# Sheet2_Inverter_GateDriver.net
KiCad netlist of a schematic drawn in Altium Designer
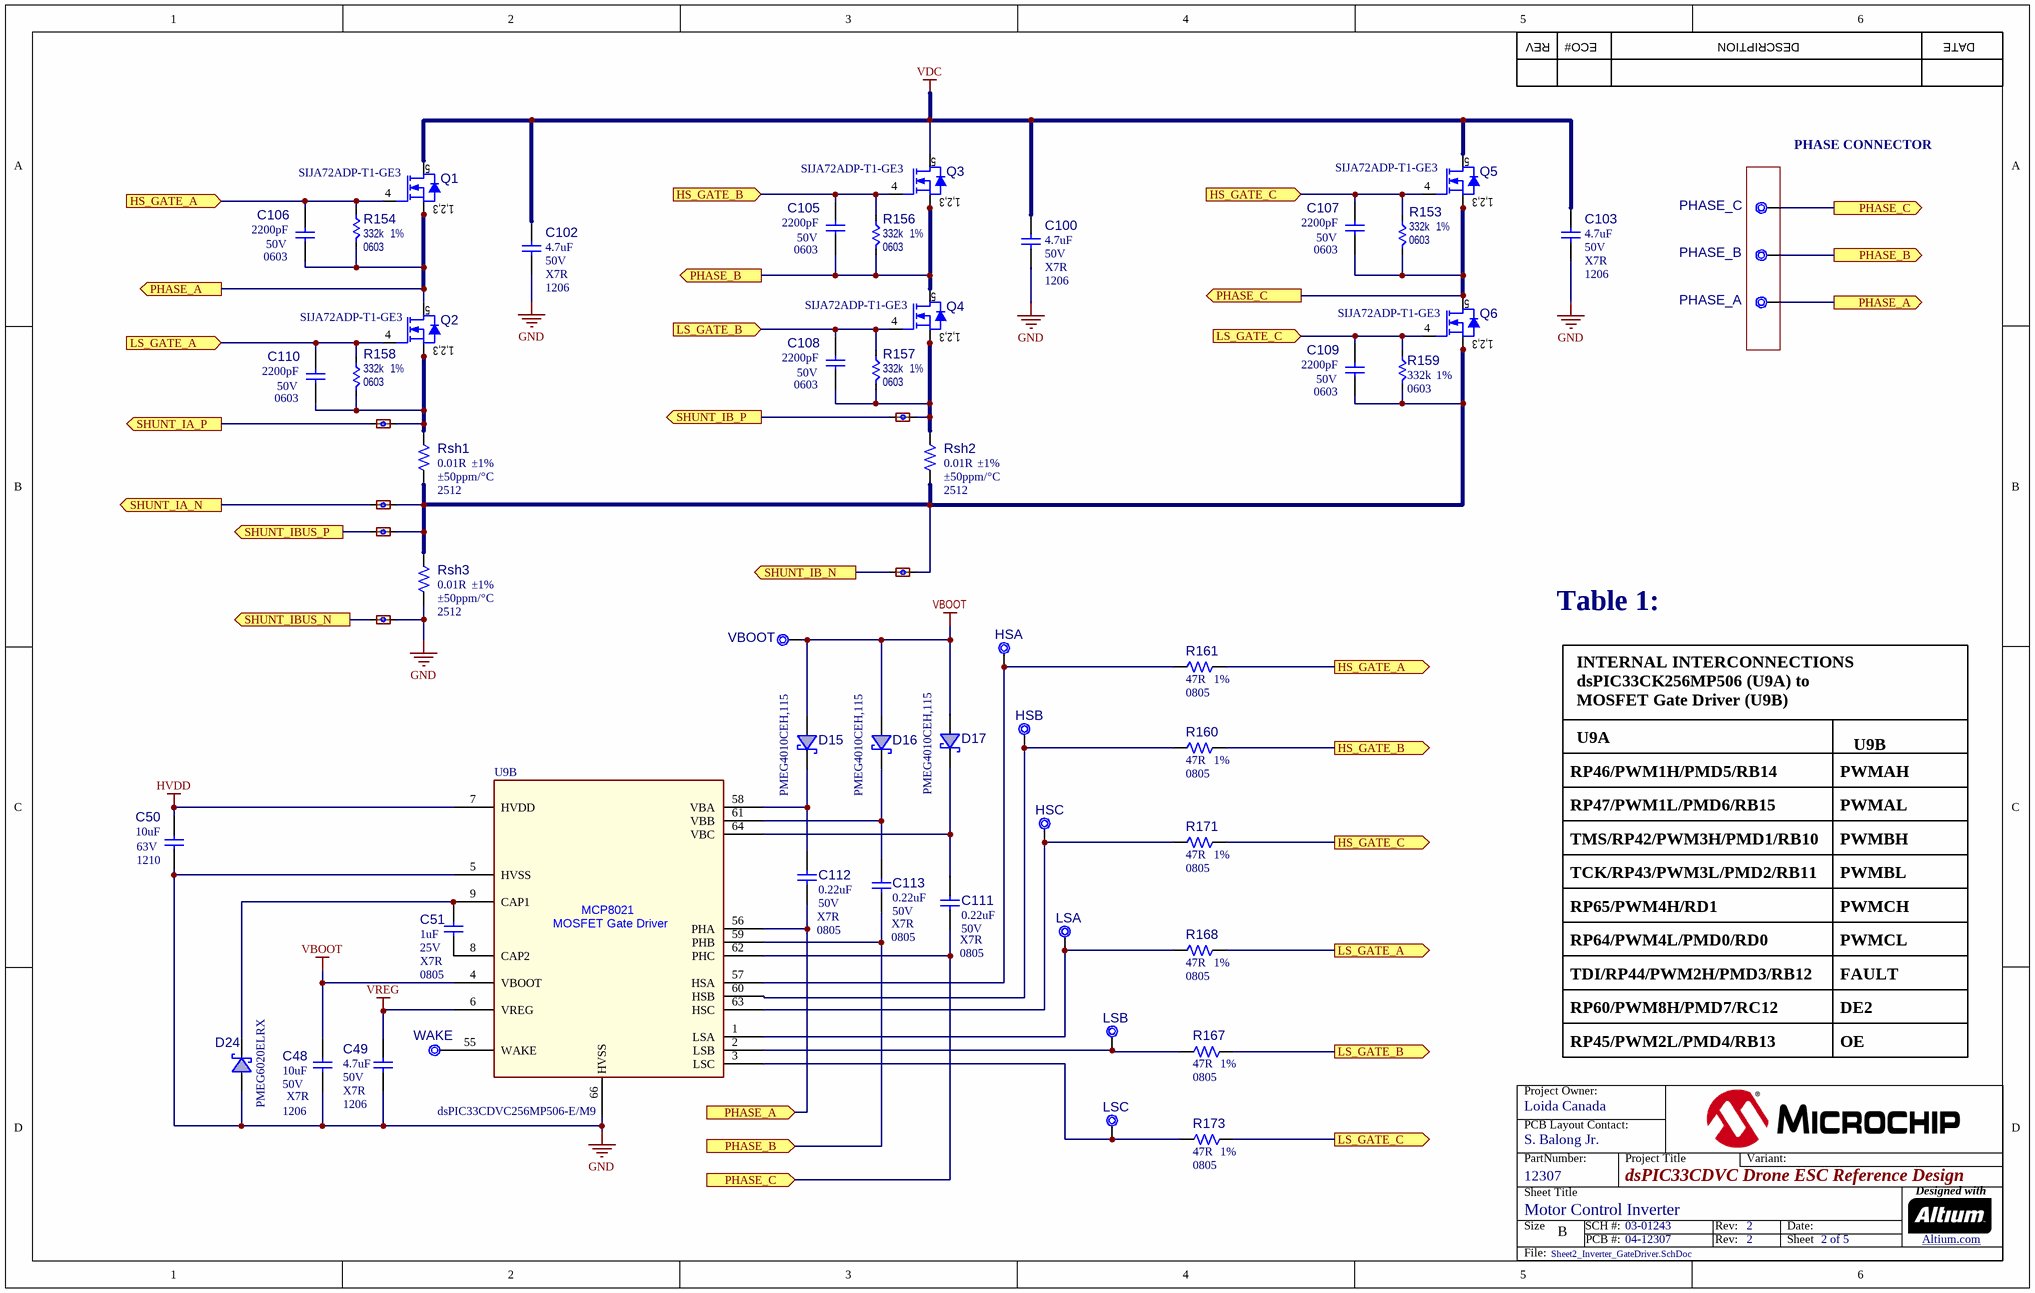
[diagram p0: Sheet2_Inverter_GateDriver.SchDoc]

(export (version "E")
  (design (tool "Eeschema 10.0.6"))
  (components
    (comp (ref "C48")
      (value "10uF")
      (footprint "CAP_C_1206")
      (fields
        (field (name "VOLTAGE") "50V")
        (field (name "PACKAGE") "1206")
        (field (name "TEMPERATURE COEFFICIENT") "X7R")
        (field (name "Comment") "Capacitor NP")
        (field (name "OWNER") "Sam Charles")
      )
      (libsource (lib "MCHP-CDB") (part "Capacitor NP"))
    )
    (comp (ref "C49")
      (value "4.7uF")
      (footprint "CAP_C_1206")
      (description "Capacitor")
      (fields
        (field (name "VOLTAGE") "50V")
        (field (name "PACKAGE") "1206")
        (field (name "TOLERANCE") "10%")
        (field (name "TEMPERATURE COEFFCIENT") "X7R")
        (field (name "Comment") "Capacitor NP")
        (field (name "OWNER") "Jairuz Agang-ang")
      )
      (libsource (lib "MCHP-CDB") (part "Capacitor NP"))
    )
    (comp (ref "C50")
      (value "10uF")
      (footprint "CAP_C_1210")
      (fields
        (field (name "VOLTAGE") "63V")
        (field (name "PACKAGE") "1210")
        (field (name "TOLERANCE") "10%")
        (field (name "Comment") "Capacitor NP")
        (field (name "OWNER") "Narasimha Murthy")
      )
      (libsource (lib "MCHP-CDB") (part "Capacitor NP"))
    )
    (comp (ref "C51")
      (value "1uF")
      (footprint "CAP_C_0805")
      (description "Capacitor")
      (fields
        (field (name "VOLTAGE") "25V")
        (field (name "PACKAGE") "0805")
        (field (name "TOLERANCE") "10%")
        (field (name "TEMPERATURE COEFFCIENT") "X7R")
        (field (name "Comment") "Capacitor NP")
        (field (name "OWNER") "Tad Ahlvers")
      )
      (libsource (lib "") (part "Capacitor NP_1"))
    )
    (comp (ref "C100")
      (value "4.7uF")
      (footprint "CAP_C_1206")
      (description "Capacitor")
      (fields
        (field (name "VOLTAGE") "50V")
        (field (name "PACKAGE") "1206")
        (field (name "TOLERANCE") "10%")
        (field (name "TEMPERATURE COEFFCIENT") "X7R")
        (field (name "Comment") "Capacitor NP")
        (field (name "OWNER") "Jairuz Agang-ang")
      )
      (libsource (lib "MCHP-CDB") (part "Capacitor NP"))
    )
    (comp (ref "C102")
      (value "4.7uF")
      (footprint "CAP_C_1206")
      (description "Capacitor")
      (fields
        (field (name "VOLTAGE") "50V")
        (field (name "PACKAGE") "1206")
        (field (name "TOLERANCE") "10%")
        (field (name "TEMPERATURE COEFFCIENT") "X7R")
        (field (name "Comment") "Capacitor NP")
        (field (name "OWNER") "Jairuz Agang-ang")
      )
      (libsource (lib "MCHP-CDB") (part "Capacitor NP"))
    )
    (comp (ref "C103")
      (value "4.7uF")
      (footprint "CAP_C_1206")
      (description "Capacitor")
      (fields
        (field (name "VOLTAGE") "50V")
        (field (name "PACKAGE") "1206")
        (field (name "TOLERANCE") "10%")
        (field (name "TEMPERATURE COEFFCIENT") "X7R")
        (field (name "Comment") "Capacitor NP")
        (field (name "OWNER") "Jairuz Agang-ang")
      )
      (libsource (lib "MCHP-CDB") (part "Capacitor NP"))
    )
    (comp (ref "C105")
      (value "2200pF")
      (footprint "CAP_C_0603")
      (fields
        (field (name "VOLTAGE") "50V")
        (field (name "PACKAGE") "0603")
        (field (name "TOLERANCE") "10%")
        (field (name "Comment") "Capacitor NP")
      )
      (libsource (lib "MCHP-CDB") (part "Capacitor NP"))
    )
    (comp (ref "C106")
      (value "2200pF")
      (footprint "CAP_C_0603")
      (fields
        (field (name "VOLTAGE") "50V")
        (field (name "PACKAGE") "0603")
        (field (name "TOLERANCE") "10%")
        (field (name "Comment") "Capacitor NP")
      )
      (libsource (lib "MCHP-CDB") (part "Capacitor NP"))
    )
    (comp (ref "C107")
      (value "2200pF")
      (footprint "CAP_C_0603")
      (fields
        (field (name "VOLTAGE") "50V")
        (field (name "PACKAGE") "0603")
        (field (name "TOLERANCE") "10%")
        (field (name "Comment") "Capacitor NP")
      )
      (libsource (lib "MCHP-CDB") (part "Capacitor NP"))
    )
    (comp (ref "C108")
      (value "2200pF")
      (footprint "CAP_C_0603")
      (fields
        (field (name "VOLTAGE") "50V")
        (field (name "PACKAGE") "0603")
        (field (name "TOLERANCE") "10%")
        (field (name "Comment") "Capacitor NP")
      )
      (libsource (lib "MCHP-CDB") (part "Capacitor NP"))
    )
    (comp (ref "C109")
      (value "2200pF")
      (footprint "CAP_C_0603")
      (fields
        (field (name "VOLTAGE") "50V")
        (field (name "PACKAGE") "0603")
        (field (name "TOLERANCE") "10%")
        (field (name "Comment") "Capacitor NP")
      )
      (libsource (lib "MCHP-CDB") (part "Capacitor NP"))
    )
    (comp (ref "C110")
      (value "2200pF")
      (footprint "CAP_C_0603")
      (fields
        (field (name "VOLTAGE") "50V")
        (field (name "PACKAGE") "0603")
        (field (name "TOLERANCE") "10%")
        (field (name "Comment") "Capacitor NP")
      )
      (libsource (lib "MCHP-CDB") (part "Capacitor NP"))
    )
    (comp (ref "C111")
      (value "0.22uF")
      (footprint "CAP_C_0805")
      (description "Capacitor")
      (fields
        (field (name "VOLTAGE") "50V")
        (field (name "PACKAGE") "0805")
        (field (name "TOLERANCE") "10%")
        (field (name "TEMPERATURE COEFFCIENT") "X7R")
        (field (name "Comment") "Capacitor NP")
      )
      (libsource (lib "MCHP-CDB") (part "Capacitor NP"))
    )
    (comp (ref "C112")
      (value "0.22uF")
      (footprint "CAP_C_0805")
      (description "Capacitor")
      (fields
        (field (name "VOLTAGE") "50V")
        (field (name "PACKAGE") "0805")
        (field (name "TOLERANCE") "10%")
        (field (name "TEMPERATURE COEFFCIENT") "X7R")
        (field (name "Comment") "Capacitor NP")
      )
      (libsource (lib "MCHP-CDB") (part "Capacitor NP"))
    )
    (comp (ref "C113")
      (value "0.22uF")
      (footprint "CAP_C_0805")
      (description "Capacitor")
      (fields
        (field (name "VOLTAGE") "50V")
        (field (name "PACKAGE") "0805")
        (field (name "TOLERANCE") "10%")
        (field (name "TEMPERATURE COEFFCIENT") "X7R")
        (field (name "Comment") "Capacitor NP")
      )
      (libsource (lib "MCHP-CDB") (part "Capacitor NP"))
    )
    (comp (ref "D15")
      (value "PMEG4010CEH,115")
      (footprint "SOD-123")
      (fields (field (name "Comment") "Diode Schottky") (field (name "OWNER") "Narasimha Murthy"))
      (libsource (lib "MCHP-CDB") (part "Diode Schottky"))
    )
    (comp (ref "D16")
      (value "PMEG4010CEH,115")
      (footprint "SOD-123")
      (fields (field (name "Comment") "Diode Schottky") (field (name "OWNER") "Narasimha Murthy"))
      (libsource (lib "MCHP-CDB") (part "Diode Schottky"))
    )
    (comp (ref "D17")
      (value "PMEG4010CEH,115")
      (footprint "SOD-123")
      (fields (field (name "Comment") "Diode Schottky") (field (name "OWNER") "Narasimha Murthy"))
      (libsource (lib "MCHP-CDB") (part "Diode Schottky"))
    )
    (comp (ref "D24")
      (value "PMEG6020ELRX")
      (footprint "SOD-123W")
      (fields (field (name "Comment") "Diode Schottky") (field (name "OWNER") "Narasimha Murthy"))
      (libsource (lib "MCHP-CDB") (part "Diode Schottky"))
    )
    (comp (ref "HSA")
      (value "Test Point No BOM")
      (footprint "TP_TH_0.7PADX0.4HOLE")
      (description "Test Point")
      (fields (field (name "OWNER") "Severino Balong Jr."))
      (libsource (lib "MCHP-CDB") (part "Test Point No BOM"))
    )
    (comp (ref "HSB")
      (value "Test Point No BOM")
      (footprint "TP_TH_0.7PADX0.4HOLE")
      (description "Test Point")
      (fields (field (name "OWNER") "Severino Balong Jr."))
      (libsource (lib "MCHP-CDB") (part "Test Point No BOM"))
    )
    (comp (ref "HSC")
      (value "Test Point No BOM")
      (footprint "TP_TH_0.7PADX0.4HOLE")
      (description "Test Point")
      (fields (field (name "OWNER") "Severino Balong Jr."))
      (libsource (lib "MCHP-CDB") (part "Test Point No BOM"))
    )
    (comp (ref "LSA")
      (value "Test Point No BOM")
      (footprint "TP_TH_0.7PADX0.4HOLE")
      (description "Test Point")
      (fields (field (name "OWNER") "Severino Balong Jr."))
      (libsource (lib "MCHP-CDB") (part "Test Point No BOM"))
    )
    (comp (ref "LSB")
      (value "Test Point No BOM")
      (footprint "TP_TH_0.7PADX0.4HOLE")
      (description "Test Point")
      (fields (field (name "OWNER") "Severino Balong Jr."))
      (libsource (lib "MCHP-CDB") (part "Test Point No BOM"))
    )
    (comp (ref "LSC")
      (value "Test Point No BOM")
      (footprint "TP_TH_0.7PADX0.4HOLE")
      (description "Test Point")
      (fields (field (name "OWNER") "Severino Balong Jr."))
      (libsource (lib "MCHP-CDB") (part "Test Point No BOM"))
    )
    (comp (ref "NT1")
      (value "Net Tie")
      (footprint "NET_TIE_0.2mmx0.5mm")
      (fields (field (name "OWNER") "Cristina Salanti"))
      (libsource (lib "MCHP-CDB") (part "Net Tie"))
    )
    (comp (ref "NT2")
      (value "Net Tie")
      (footprint "NET_TIE_0.2mmx0.5mm")
      (fields (field (name "OWNER") "Cristina Salanti"))
      (libsource (lib "MCHP-CDB") (part "Net Tie"))
    )
    (comp (ref "NT3")
      (value "Net Tie")
      (footprint "NET_TIE_0.2mmx0.5mm")
      (fields (field (name "OWNER") "Cristina Salanti"))
      (libsource (lib "MCHP-CDB") (part "Net Tie"))
    )
    (comp (ref "NT4")
      (value "Net Tie")
      (footprint "NET_TIE_0.2mmx0.5mm")
      (fields (field (name "OWNER") "Cristina Salanti"))
      (libsource (lib "MCHP-CDB") (part "Net Tie"))
    )
    (comp (ref "NT5")
      (value "Net Tie")
      (footprint "NET_TIE_0.2mmx0.5mm")
      (fields (field (name "OWNER") "Cristina Salanti"))
      (libsource (lib "MCHP-CDB") (part "Net Tie"))
    )
    (comp (ref "NT6")
      (value "Net Tie")
      (footprint "NET_TIE_0.2mmx0.5mm")
      (fields (field (name "OWNER") "Cristina Salanti"))
      (libsource (lib "MCHP-CDB") (part "Net Tie"))
    )
    (comp (ref "PHASE_A")
      (value "Test Point No BOM")
      (footprint "TP_3.0X2.3X1.3HOLE")
      (description "Test Point")
      (fields (field (name "OWNER") "Severino Balong Jr."))
      (libsource (lib "MCHP-CDB") (part "Test Point No BOM"))
    )
    (comp (ref "PHASE_B")
      (value "Test Point No BOM")
      (footprint "TP_3.0X2.3X1.3HOLE")
      (description "Test Point")
      (fields (field (name "OWNER") "Severino Balong Jr."))
      (libsource (lib "MCHP-CDB") (part "Test Point No BOM"))
    )
    (comp (ref "PHASE_C")
      (value "Test Point No BOM")
      (footprint "TP_3.0X2.3X1.3HOLE")
      (description "Test Point")
      (fields (field (name "OWNER") "Severino Balong Jr."))
      (libsource (lib "MCHP-CDB") (part "Test Point No BOM"))
    )
    (comp (ref "Q1")
      (value "SIJA72ADP-T1-GE3")
      (footprint "PPAK_SO-8L")
      (description "Transistor MOS")
      (fields
        (field (name "POWER") "4.8W")
        (field (name "VOLTAGE") "40V")
        (field (name "OWNER") "Cristina Salanti")
      )
      (libsource (lib "MCHP-CDB") (part "Transistor MOS-N SSSGD"))
    )
    (comp (ref "Q2")
      (value "SIJA72ADP-T1-GE3")
      (footprint "PPAK_SO-8L")
      (description "Transistor MOS")
      (fields
        (field (name "POWER") "4.8W")
        (field (name "VOLTAGE") "40V")
        (field (name "OWNER") "Cristina Salanti")
      )
      (libsource (lib "MCHP-CDB") (part "Transistor MOS-N SSSGD"))
    )
    (comp (ref "Q3")
      (value "SIJA72ADP-T1-GE3")
      (footprint "PPAK_SO-8L")
      (description "Transistor MOS")
      (fields
        (field (name "POWER") "4.8W")
        (field (name "VOLTAGE") "40V")
        (field (name "OWNER") "Cristina Salanti")
      )
      (libsource (lib "MCHP-CDB") (part "Transistor MOS-N SSSGD"))
    )
    (comp (ref "Q4")
      (value "SIJA72ADP-T1-GE3")
      (footprint "PPAK_SO-8L")
      (description "Transistor MOS")
      (fields
        (field (name "POWER") "4.8W")
        (field (name "VOLTAGE") "40V")
        (field (name "OWNER") "Cristina Salanti")
      )
      (libsource (lib "MCHP-CDB") (part "Transistor MOS-N SSSGD"))
    )
    (comp (ref "Q5")
      (value "SIJA72ADP-T1-GE3")
      (footprint "PPAK_SO-8L")
      (description "Transistor MOS")
      (fields
        (field (name "POWER") "4.8W")
        (field (name "VOLTAGE") "40V")
        (field (name "OWNER") "Cristina Salanti")
      )
      (libsource (lib "MCHP-CDB") (part "Transistor MOS-N SSSGD"))
    )
    (comp (ref "Q6")
      (value "SIJA72ADP-T1-GE3")
      (footprint "PPAK_SO-8L")
      (description "Transistor MOS")
      (fields
        (field (name "POWER") "4.8W")
        (field (name "VOLTAGE") "40V")
        (field (name "OWNER") "Cristina Salanti")
      )
      (libsource (lib "MCHP-CDB") (part "Transistor MOS-N SSSGD"))
    )
    (comp (ref "R153")
      (value "332k")
      (footprint "RES_C_0603")
      (description "Resistor")
      (fields
        (field (name "PACKAGE") "0603")
        (field (name "TOLERANCE") "1%")
        (field (name "VOLTAGE") "75V")
        (field (name "POWER") "1/10W")
        (field (name "OWNER") "Bogdan P (M91398)")
      )
      (libsource (lib "") (part "Resistor_1"))
    )
    (comp (ref "R154")
      (value "332k")
      (footprint "RES_C_0603")
      (description "Resistor")
      (fields
        (field (name "PACKAGE") "0603")
        (field (name "TOLERANCE") "1%")
        (field (name "VOLTAGE") "75V")
        (field (name "POWER") "1/10W")
        (field (name "OWNER") "Bogdan P (M91398)")
      )
      (libsource (lib "") (part "Resistor_1"))
    )
    (comp (ref "R156")
      (value "332k")
      (footprint "RES_C_0603")
      (description "Resistor")
      (fields
        (field (name "PACKAGE") "0603")
        (field (name "TOLERANCE") "1%")
        (field (name "VOLTAGE") "75V")
        (field (name "POWER") "1/10W")
        (field (name "OWNER") "Bogdan P (M91398)")
      )
      (libsource (lib "") (part "Resistor_1"))
    )
    (comp (ref "R157")
      (value "332k")
      (footprint "RES_C_0603")
      (description "Resistor")
      (fields
        (field (name "PACKAGE") "0603")
        (field (name "TOLERANCE") "1%")
        (field (name "VOLTAGE") "75V")
        (field (name "POWER") "1/10W")
        (field (name "OWNER") "Bogdan P (M91398)")
      )
      (libsource (lib "") (part "Resistor_1"))
    )
    (comp (ref "R158")
      (value "332k")
      (footprint "RES_C_0603")
      (description "Resistor")
      (fields
        (field (name "PACKAGE") "0603")
        (field (name "TOLERANCE") "1%")
        (field (name "VOLTAGE") "75V")
        (field (name "POWER") "1/10W")
        (field (name "OWNER") "Bogdan P (M91398)")
      )
      (libsource (lib "") (part "Resistor_1"))
    )
    (comp (ref "R159")
      (value "332k")
      (footprint "RES_C_0603")
      (description "Resistor")
      (fields
        (field (name "PACKAGE") "0603")
        (field (name "TOLERANCE") "1%")
        (field (name "VOLTAGE") "75V")
        (field (name "POWER") "1/10W")
        (field (name "OWNER") "Bogdan P (M91398)")
      )
      (libsource (lib "") (part "Resistor_1"))
    )
    (comp (ref "R160")
      (value "47R")
      (footprint "RES_C_0805")
      (description "Resistor")
      (fields
        (field (name "PACKAGE") "0805")
        (field (name "TOLERANCE") "1%")
        (field (name "POWER") "1/8W")
        (field (name "OWNER") "Henry de Villiers")
      )
      (libsource (lib "MCHP-CDB") (part "Resistor"))
    )
    (comp (ref "R161")
      (value "47R")
      (footprint "RES_C_0805")
      (description "Resistor")
      (fields
        (field (name "PACKAGE") "0805")
        (field (name "TOLERANCE") "1%")
        (field (name "POWER") "1/8W")
        (field (name "OWNER") "Henry de Villiers")
      )
      (libsource (lib "MCHP-CDB") (part "Resistor"))
    )
    (comp (ref "R167")
      (value "47R")
      (footprint "RES_C_0805")
      (description "Resistor")
      (fields
        (field (name "PACKAGE") "0805")
        (field (name "TOLERANCE") "1%")
        (field (name "POWER") "1/8W")
        (field (name "OWNER") "Henry de Villiers")
      )
      (libsource (lib "MCHP-CDB") (part "Resistor"))
    )
    (comp (ref "R168")
      (value "47R")
      (footprint "RES_C_0805")
      (description "Resistor")
      (fields
        (field (name "PACKAGE") "0805")
        (field (name "TOLERANCE") "1%")
        (field (name "POWER") "1/8W")
        (field (name "OWNER") "Henry de Villiers")
      )
      (libsource (lib "MCHP-CDB") (part "Resistor"))
    )
    (comp (ref "R171")
      (value "47R")
      (footprint "RES_C_0805")
      (description "Resistor")
      (fields
        (field (name "PACKAGE") "0805")
        (field (name "TOLERANCE") "1%")
        (field (name "POWER") "1/8W")
        (field (name "OWNER") "Henry de Villiers")
      )
      (libsource (lib "MCHP-CDB") (part "Resistor"))
    )
    (comp (ref "R173")
      (value "47R")
      (footprint "RES_C_0805")
      (description "Resistor")
      (fields
        (field (name "PACKAGE") "0805")
        (field (name "TOLERANCE") "1%")
        (field (name "POWER") "1/8W")
        (field (name "OWNER") "Henry de Villiers")
      )
      (libsource (lib "MCHP-CDB") (part "Resistor"))
    )
    (comp (ref "Rsh1")
      (value "0.01R")
      (footprint "RES_C_2512")
      (description "Resistor")
      (fields
        (field (name "PACKAGE") "2512")
        (field (name "TOLERANCE") "±1%")
        (field (name "TEMPERATURE COEFFCIENT") "±50ppm/°C")
        (field (name "POWER") "3W")
        (field (name "OWNER") "Narasimha Murthy")
      )
      (libsource (lib "MCHP-CDB") (part "Resistor"))
    )
    (comp (ref "Rsh2")
      (value "0.01R")
      (footprint "RES_C_2512")
      (description "Resistor")
      (fields
        (field (name "PACKAGE") "2512")
        (field (name "TOLERANCE") "±1%")
        (field (name "TEMPERATURE COEFFCIENT") "±50ppm/°C")
        (field (name "POWER") "3W")
        (field (name "OWNER") "Narasimha Murthy")
      )
      (libsource (lib "MCHP-CDB") (part "Resistor"))
    )
    (comp (ref "Rsh3")
      (value "0.01R")
      (footprint "RES_C_2512")
      (description "Resistor")
      (fields
        (field (name "PACKAGE") "2512")
        (field (name "TOLERANCE") "±1%")
        (field (name "TEMPERATURE COEFFCIENT") "±50ppm/°C")
        (field (name "POWER") "3W")
        (field (name "OWNER") "Narasimha Murthy")
      )
      (libsource (lib "MCHP-CDB") (part "Resistor"))
    )
    (comp (ref "U9")
      (value "dsPIC33CDVC256MP506-E/M9")
      (footprint "QFN-64_9X9_3EP_M9")
      (fields
        (field (name "Comment") "dsPIC33CDVC256MP506_VGQFN-64")
        (field (name "OWNER") "Narasimha Murthy")
      )
      (libsource (lib "MCHP-CDB") (part "dsPIC33CDVC256MP506_VGQFN-64"))
    )
    (comp (ref "VBOOT")
      (value "Test Point No BOM")
      (footprint "TP_TH_0.7PADX0.4HOLE")
      (description "Test Point")
      (fields (field (name "OWNER") "Severino Balong Jr."))
      (libsource (lib "MCHP-CDB") (part "Test Point No BOM"))
    )
    (comp (ref "WAKE")
      (value "Test Point No BOM")
      (footprint "CON_TP_SMD_D25mil_NoSilk")
      (description "Test Point")
      (fields (field (name "OWNER") "James Boomer"))
      (libsource (lib "") (part "Test Point No BOM_1"))
    )
  )
  (nets
    (net (code "1") (name "/HS_GATE_A") (class "Default")
      (node (ref "C106") (pin "2") (pinfunction "2_2") (pintype "passive"))
      (node (ref "Q1") (pin "4") (pinfunction "G_4") (pintype "passive"))
      (node (ref "R154") (pin "1") (pinfunction "1_1") (pintype "passive"))
      (node (ref "R161") (pin "2") (pinfunction "2_2") (pintype "passive"))
    )
    (net (code "2") (name "/HS_GATE_B") (class "Default")
      (node (ref "C105") (pin "2") (pinfunction "2_2") (pintype "passive"))
      (node (ref "Q3") (pin "4") (pinfunction "G_4") (pintype "passive"))
      (node (ref "R156") (pin "1") (pinfunction "1_1") (pintype "passive"))
      (node (ref "R160") (pin "2") (pinfunction "2_2") (pintype "passive"))
    )
    (net (code "3") (name "/HS_GATE_C") (class "Default")
      (node (ref "C107") (pin "2") (pinfunction "2_2") (pintype "passive"))
      (node (ref "Q5") (pin "4") (pinfunction "G_4") (pintype "passive"))
      (node (ref "R153") (pin "1") (pinfunction "1_1") (pintype "passive"))
      (node (ref "R171") (pin "2") (pinfunction "2_2") (pintype "passive"))
    )
    (net (code "4") (name "/LS_GATE_A") (class "Default")
      (node (ref "C110") (pin "2") (pinfunction "2_2") (pintype "passive"))
      (node (ref "Q2") (pin "4") (pinfunction "G_4") (pintype "passive"))
      (node (ref "R158") (pin "1") (pinfunction "1_1") (pintype "passive"))
      (node (ref "R168") (pin "2") (pinfunction "2_2") (pintype "passive"))
    )
    (net (code "5") (name "/LS_GATE_B") (class "Default")
      (node (ref "C108") (pin "2") (pinfunction "2_2") (pintype "passive"))
      (node (ref "Q4") (pin "4") (pinfunction "G_4") (pintype "passive"))
      (node (ref "R157") (pin "1") (pinfunction "1_1") (pintype "passive"))
      (node (ref "R167") (pin "2") (pinfunction "2_2") (pintype "passive"))
    )
    (net (code "6") (name "/LS_GATE_C") (class "Default")
      (node (ref "C109") (pin "2") (pinfunction "2_2") (pintype "passive"))
      (node (ref "Q6") (pin "4") (pinfunction "G_4") (pintype "passive"))
      (node (ref "R159") (pin "1") (pinfunction "1_1") (pintype "passive"))
      (node (ref "R173") (pin "2") (pinfunction "2_2") (pintype "passive"))
    )
    (net (code "7") (name "/PHASE_A") (class "Default")
      (node (ref "C106") (pin "1") (pinfunction "1_1") (pintype "passive"))
      (node (ref "C112") (pin "1") (pinfunction "1_1") (pintype "passive"))
      (node (ref "PHASE_A") (pin "1") (pinfunction "1_1") (pintype "passive"))
      (node (ref "Q1") (pin "1") (pinfunction "S_1") (pintype "passive"))
      (node (ref "Q1") (pin "2") (pinfunction "S_2") (pintype "passive"))
      (node (ref "Q1") (pin "3") (pinfunction "S_3") (pintype "passive"))
      (node (ref "Q2") (pin "5") (pinfunction "D_5") (pintype "passive"))
      (node (ref "R154") (pin "2") (pinfunction "2_2") (pintype "passive"))
      (node (ref "U9") (pin "56") (pinfunction "PHA_56") (pintype "power_in"))
    )
    (net (code "8") (name "/PHASE_B") (class "Default")
      (node (ref "C105") (pin "1") (pinfunction "1_1") (pintype "passive"))
      (node (ref "C113") (pin "1") (pinfunction "1_1") (pintype "passive"))
      (node (ref "PHASE_B") (pin "1") (pinfunction "1_1") (pintype "passive"))
      (node (ref "Q3") (pin "1") (pinfunction "S_1") (pintype "passive"))
      (node (ref "Q3") (pin "2") (pinfunction "S_2") (pintype "passive"))
      (node (ref "Q3") (pin "3") (pinfunction "S_3") (pintype "passive"))
      (node (ref "Q4") (pin "5") (pinfunction "D_5") (pintype "passive"))
      (node (ref "R156") (pin "2") (pinfunction "2_2") (pintype "passive"))
      (node (ref "U9") (pin "59") (pinfunction "PHB_59") (pintype "passive"))
    )
    (net (code "9") (name "/PHASE_C") (class "Default")
      (node (ref "C107") (pin "1") (pinfunction "1_1") (pintype "passive"))
      (node (ref "C111") (pin "1") (pinfunction "1_1") (pintype "passive"))
      (node (ref "PHASE_C") (pin "1") (pinfunction "1_1") (pintype "passive"))
      (node (ref "Q5") (pin "1") (pinfunction "S_1") (pintype "passive"))
      (node (ref "Q5") (pin "2") (pinfunction "S_2") (pintype "passive"))
      (node (ref "Q5") (pin "3") (pinfunction "S_3") (pintype "passive"))
      (node (ref "Q6") (pin "5") (pinfunction "D_5") (pintype "passive"))
      (node (ref "R153") (pin "2") (pinfunction "2_2") (pintype "passive"))
      (node (ref "U9") (pin "62") (pinfunction "PHC_62") (pintype "passive"))
    )
    (net (code "10") (name "/SHUNT_IA_N") (class "Default")
      (node (ref "NT3") (pin "1") (pinfunction "1_1") (pintype "passive"))
    )
    (net (code "11") (name "/SHUNT_IA_P") (class "Default")
      (node (ref "NT2") (pin "1") (pinfunction "1_1") (pintype "passive"))
    )
    (net (code "12") (name "/SHUNT_IBUS_N") (class "Default")
      (node (ref "NT6") (pin "1") (pinfunction "1_1") (pintype "passive"))
    )
    (net (code "13") (name "/SHUNT_IBUS_P") (class "Default")
      (node (ref "NT4") (pin "1") (pinfunction "1_1") (pintype "passive"))
    )
    (net (code "14") (name "/SHUNT_IB_N") (class "Default")
      (node (ref "NT5") (pin "1") (pinfunction "1_1") (pintype "passive"))
    )
    (net (code "15") (name "/SHUNT_IB_P") (class "Default")
      (node (ref "NT1") (pin "1") (pinfunction "1_1") (pintype "passive"))
    )
    (net (code "16") (name "GND") (class "Default")
      (node (ref "C100") (pin "2") (pinfunction "2_2") (pintype "passive"))
      (node (ref "C102") (pin "2") (pinfunction "2_2") (pintype "passive"))
      (node (ref "C103") (pin "2") (pinfunction "2_2") (pintype "passive"))
      (node (ref "C48") (pin "2") (pinfunction "2_2") (pintype "passive"))
      (node (ref "C49") (pin "2") (pinfunction "2_2") (pintype "passive"))
      (node (ref "C50") (pin "1") (pinfunction "1_1") (pintype "passive"))
      (node (ref "D24") (pin "1") (pinfunction "A_1") (pintype "passive"))
      (node (ref "NT6") (pin "2") (pinfunction "2_2") (pintype "passive"))
      (node (ref "Rsh3") (pin "1") (pinfunction "1_1") (pintype "passive"))
      (node (ref "U9") (pin "5") (pinfunction "HVSS_5") (pintype "power_in"))
      (node (ref "U9") (pin "66") (pinfunction "HVSS_66") (pintype "power_in"))
    )
    (net (code "17") (name "HVDD") (class "Default")
      (node (ref "C50") (pin "2") (pinfunction "2_2") (pintype "passive"))
      (node (ref "U9") (pin "7") (pinfunction "HVDD_7") (pintype "power_in"))
    )
    (net (code "18") (name "Net-(C108-Pad1)") (class "Default")
      (node (ref "C108") (pin "1") (pinfunction "1_1") (pintype "passive"))
      (node (ref "NT1") (pin "2") (pinfunction "2_2") (pintype "passive"))
      (node (ref "Q4") (pin "1") (pinfunction "S_1") (pintype "passive"))
      (node (ref "Q4") (pin "2") (pinfunction "S_2") (pintype "passive"))
      (node (ref "Q4") (pin "3") (pinfunction "S_3") (pintype "passive"))
      (node (ref "R157") (pin "2") (pinfunction "2_2") (pintype "passive"))
      (node (ref "Rsh2") (pin "2") (pinfunction "2_2") (pintype "passive"))
    )
    (net (code "19") (name "Net-(C109-Pad1)") (class "Default")
      (node (ref "C109") (pin "1") (pinfunction "1_1") (pintype "passive"))
      (node (ref "NT3") (pin "2") (pinfunction "2_2") (pintype "passive"))
      (node (ref "NT4") (pin "2") (pinfunction "2_2") (pintype "passive"))
      (node (ref "NT5") (pin "2") (pinfunction "2_2") (pintype "passive"))
      (node (ref "Q6") (pin "1") (pinfunction "S_1") (pintype "passive"))
      (node (ref "Q6") (pin "2") (pinfunction "S_2") (pintype "passive"))
      (node (ref "Q6") (pin "3") (pinfunction "S_3") (pintype "passive"))
      (node (ref "R159") (pin "2") (pinfunction "2_2") (pintype "passive"))
      (node (ref "Rsh1") (pin "1") (pinfunction "1_1") (pintype "passive"))
      (node (ref "Rsh2") (pin "1") (pinfunction "1_1") (pintype "passive"))
      (node (ref "Rsh3") (pin "2") (pinfunction "2_2") (pintype "passive"))
    )
    (net (code "20") (name "Net-(C110-Pad1)") (class "Default")
      (node (ref "C110") (pin "1") (pinfunction "1_1") (pintype "passive"))
      (node (ref "NT2") (pin "2") (pinfunction "2_2") (pintype "passive"))
      (node (ref "Q2") (pin "1") (pinfunction "S_1") (pintype "passive"))
      (node (ref "Q2") (pin "2") (pinfunction "S_2") (pintype "passive"))
      (node (ref "Q2") (pin "3") (pinfunction "S_3") (pintype "passive"))
      (node (ref "R158") (pin "2") (pinfunction "2_2") (pintype "passive"))
      (node (ref "Rsh1") (pin "2") (pinfunction "2_2") (pintype "passive"))
    )
    (net (code "21") (name "Net-(D15-K)") (class "Default")
      (node (ref "C112") (pin "2") (pinfunction "2_2") (pintype "passive"))
      (node (ref "D15") (pin "2") (pinfunction "K_2") (pintype "passive"))
      (node (ref "U9") (pin "58") (pinfunction "VBA_58") (pintype "passive"))
    )
    (net (code "22") (name "Net-(D16-K)") (class "Default")
      (node (ref "C113") (pin "2") (pinfunction "2_2") (pintype "passive"))
      (node (ref "D16") (pin "2") (pinfunction "K_2") (pintype "passive"))
      (node (ref "U9") (pin "61") (pinfunction "VBB_61") (pintype "passive"))
    )
    (net (code "23") (name "Net-(D17-K)") (class "Default")
      (node (ref "C111") (pin "2") (pinfunction "2_2") (pintype "passive"))
      (node (ref "D17") (pin "2") (pinfunction "K_2") (pintype "passive"))
      (node (ref "U9") (pin "64") (pinfunction "VBC_64") (pintype "passive"))
    )
    (net (code "24") (name "Net-(D24-K)") (class "Default")
      (node (ref "C51") (pin "2") (pinfunction "2_2") (pintype "passive"))
      (node (ref "D24") (pin "2") (pinfunction "K_2") (pintype "passive"))
      (node (ref "U9") (pin "9") (pinfunction "CAP1_9") (pintype "passive"))
    )
    (net (code "25") (name "Net-(U9B-CAP2)") (class "Default")
      (node (ref "C51") (pin "1") (pinfunction "1_1") (pintype "passive"))
      (node (ref "U9") (pin "8") (pinfunction "CAP2_8") (pintype "passive"))
    )
    (net (code "26") (name "Net-(U9B-HSA)") (class "Default")
      (node (ref "HSA") (pin "1") (pinfunction "1_1") (pintype "passive"))
      (node (ref "R161") (pin "1") (pinfunction "1_1") (pintype "passive"))
      (node (ref "U9") (pin "57") (pinfunction "HSA_57") (pintype "power_in"))
    )
    (net (code "27") (name "Net-(U9B-HSB)") (class "Default")
      (node (ref "HSB") (pin "1") (pinfunction "1_1") (pintype "passive"))
      (node (ref "R160") (pin "1") (pinfunction "1_1") (pintype "passive"))
      (node (ref "U9") (pin "60") (pinfunction "HSB_60") (pintype "passive"))
    )
    (net (code "28") (name "Net-(U9B-HSC)") (class "Default")
      (node (ref "HSC") (pin "1") (pinfunction "1_1") (pintype "passive"))
      (node (ref "R171") (pin "1") (pinfunction "1_1") (pintype "passive"))
      (node (ref "U9") (pin "63") (pinfunction "HSC_63") (pintype "passive"))
    )
    (net (code "29") (name "Net-(U9B-LSA)") (class "Default")
      (node (ref "LSA") (pin "1") (pinfunction "1_1") (pintype "passive"))
      (node (ref "R168") (pin "1") (pinfunction "1_1") (pintype "passive"))
      (node (ref "U9") (pin "1") (pinfunction "LSA_1") (pintype "passive"))
    )
    (net (code "30") (name "Net-(U9B-LSB)") (class "Default")
      (node (ref "LSB") (pin "1") (pinfunction "1_1") (pintype "passive"))
      (node (ref "R167") (pin "1") (pinfunction "1_1") (pintype "passive"))
      (node (ref "U9") (pin "2") (pinfunction "LSB_2") (pintype "passive"))
    )
    (net (code "31") (name "Net-(U9B-LSC)") (class "Default")
      (node (ref "LSC") (pin "1") (pinfunction "1_1") (pintype "passive"))
      (node (ref "R173") (pin "1") (pinfunction "1_1") (pintype "passive"))
      (node (ref "U9") (pin "3") (pinfunction "LSC_3") (pintype "passive"))
    )
    (net (code "32") (name "Net-(U9B-WAKE)") (class "Default")
      (node (ref "U9") (pin "55") (pinfunction "WAKE_55") (pintype "passive"))
      (node (ref "WAKE") (pin "1") (pinfunction "1_1") (pintype "passive"))
    )
    (net (code "33") (name "VBOOT") (class "Default")
      (node (ref "C48") (pin "1") (pinfunction "1_1") (pintype "passive"))
      (node (ref "D15") (pin "1") (pinfunction "A_1") (pintype "passive"))
      (node (ref "D16") (pin "1") (pinfunction "A_1") (pintype "passive"))
      (node (ref "D17") (pin "1") (pinfunction "A_1") (pintype "passive"))
      (node (ref "U9") (pin "4") (pinfunction "VBOOT_4") (pintype "passive"))
      (node (ref "VBOOT") (pin "1") (pinfunction "1_1") (pintype "passive"))
    )
    (net (code "34") (name "VDC") (class "Default")
      (node (ref "C100") (pin "1") (pinfunction "1_1") (pintype "passive"))
      (node (ref "C102") (pin "1") (pinfunction "1_1") (pintype "passive"))
      (node (ref "C103") (pin "1") (pinfunction "1_1") (pintype "passive"))
      (node (ref "Q1") (pin "5") (pinfunction "D_5") (pintype "passive"))
      (node (ref "Q3") (pin "5") (pinfunction "D_5") (pintype "passive"))
      (node (ref "Q5") (pin "5") (pinfunction "D_5") (pintype "passive"))
    )
    (net (code "35") (name "VREG") (class "Default")
      (node (ref "C49") (pin "1") (pinfunction "1_1") (pintype "passive"))
      (node (ref "U9") (pin "6") (pinfunction "VREG_6") (pintype "passive"))
    )
  )
)
